# Sch.net
KiCad netlist of a schematic drawn in Altium Designer
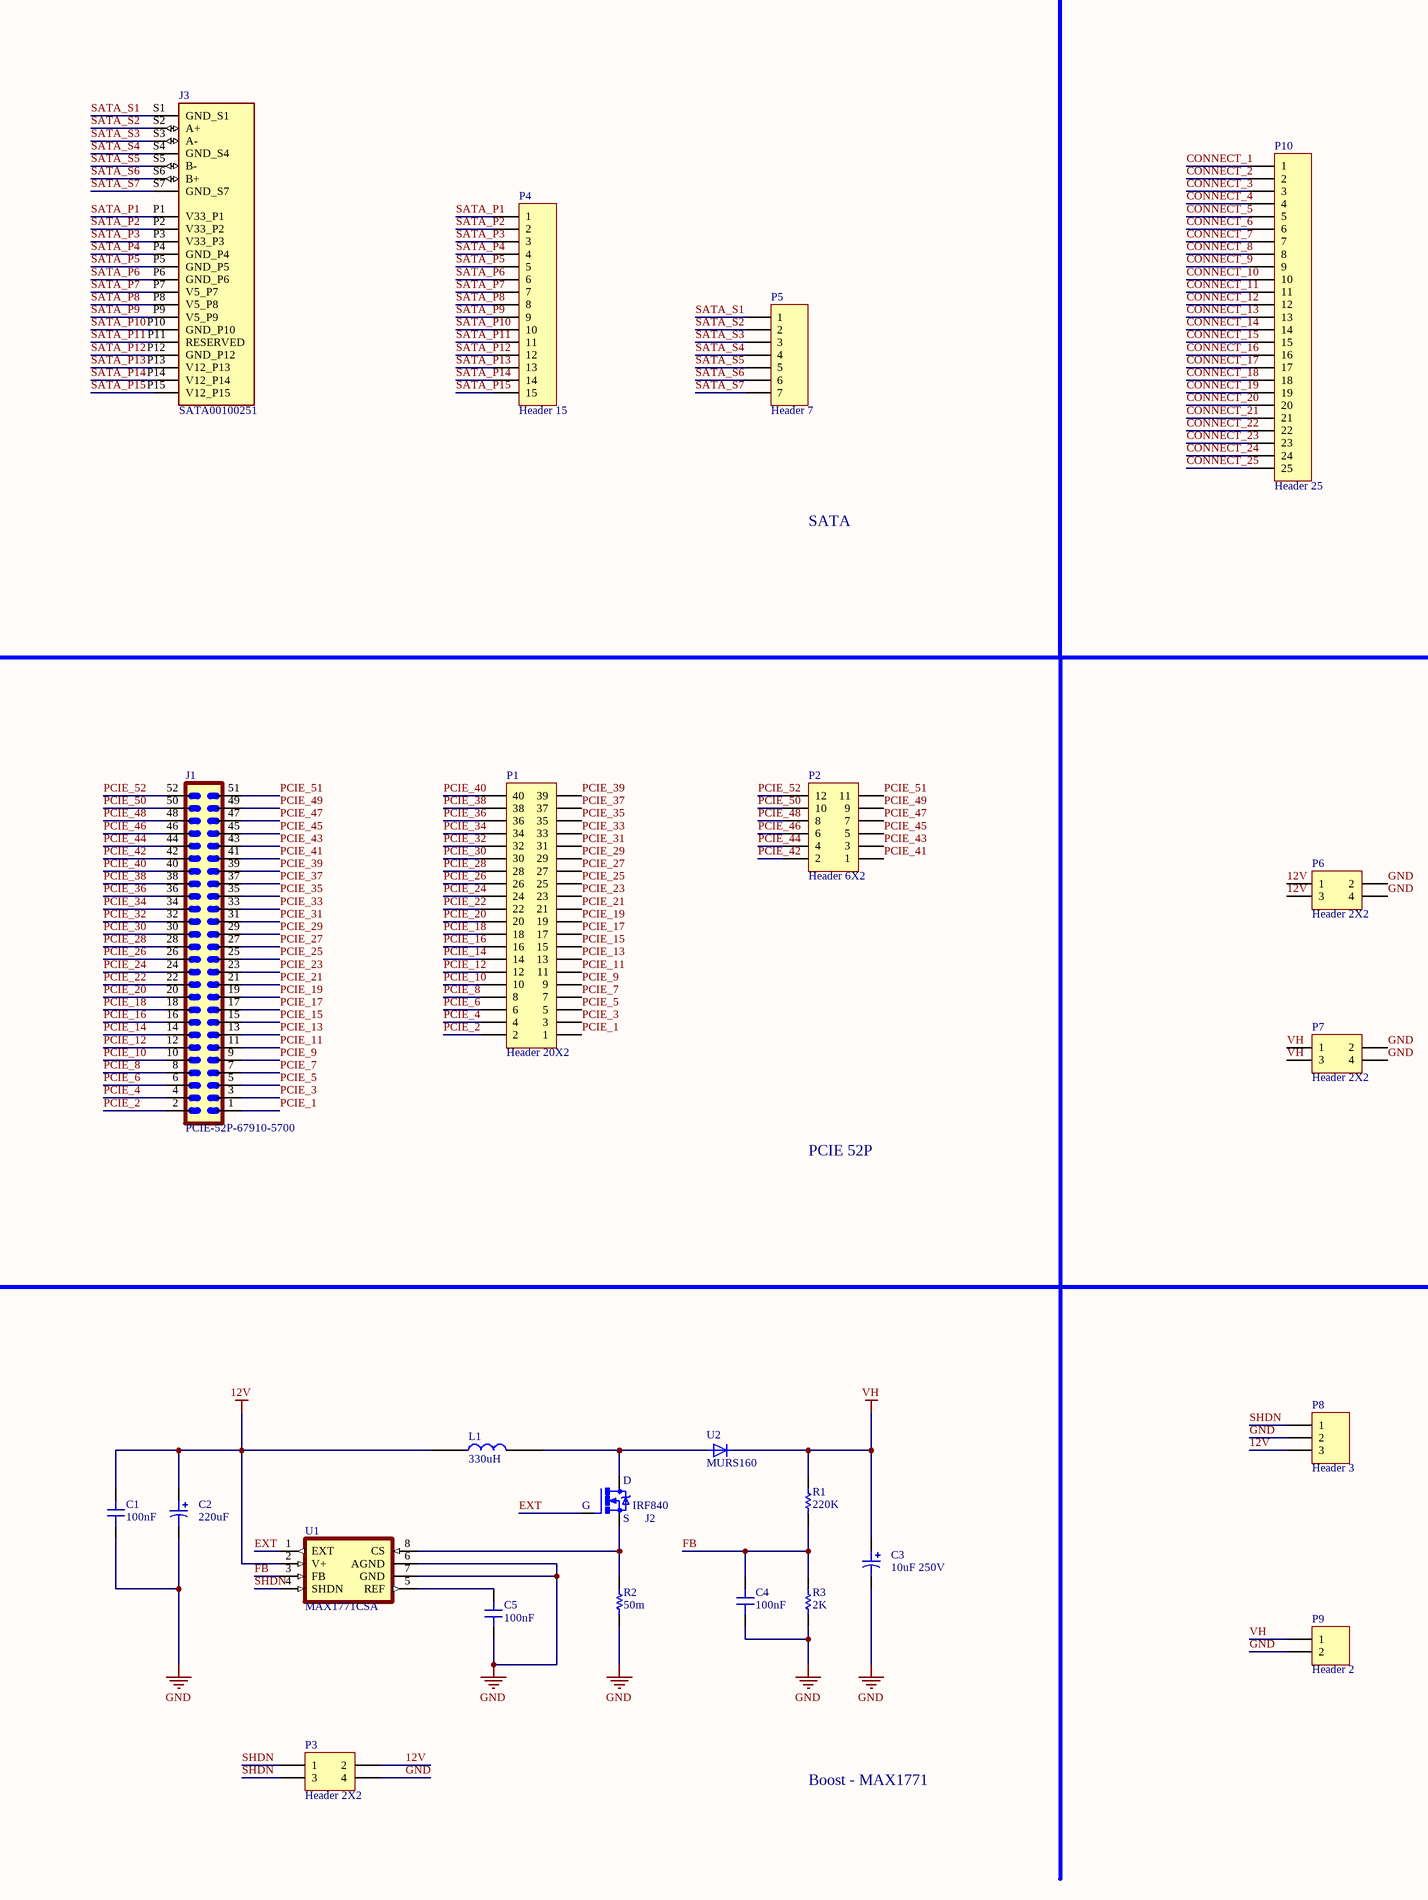
[diagram p0: Sch.SchDoc, left]
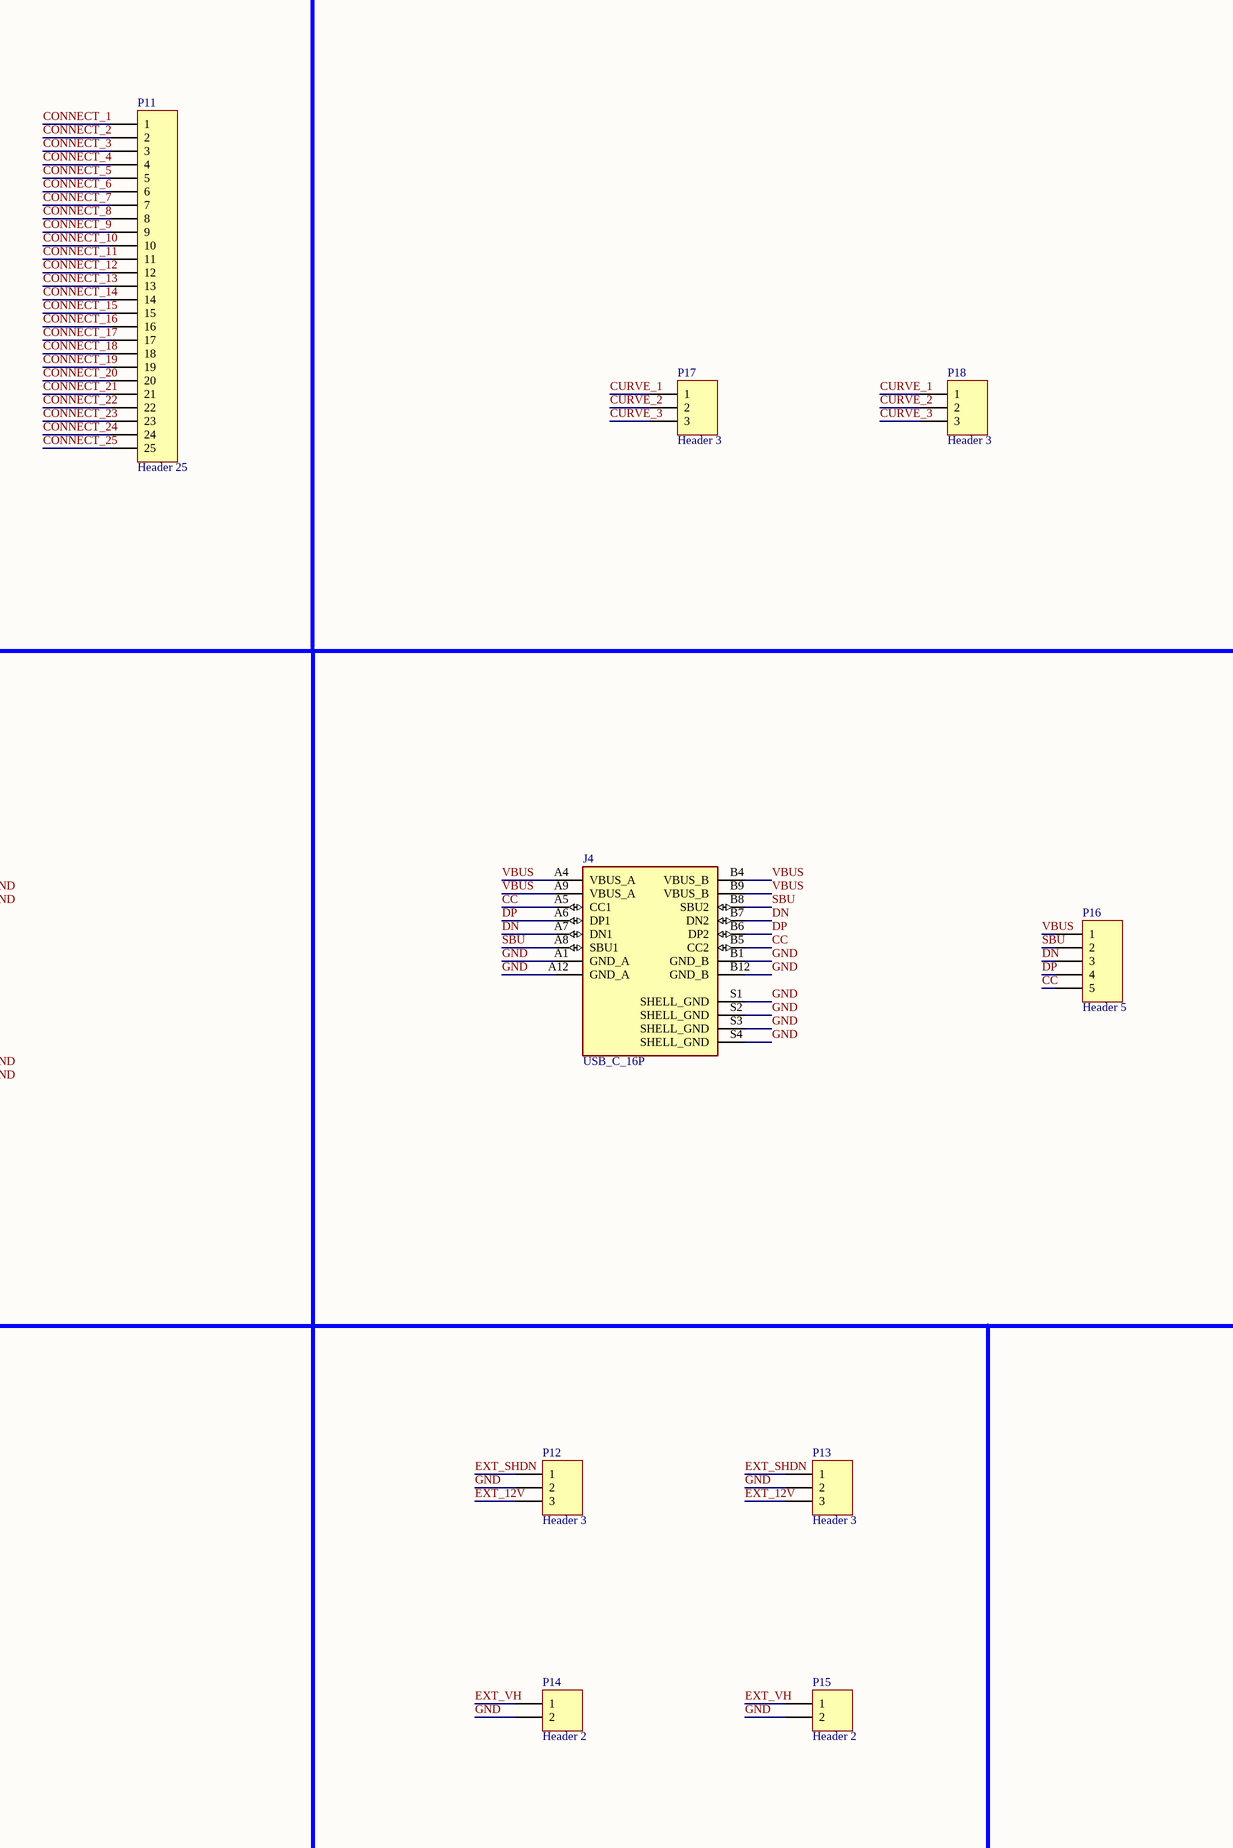
[diagram p1: Sch.SchDoc, right]

(export (version "E")
  (design (tool "Eeschema 10.0.6"))
  (components
    (comp (ref "C1") (value "100nF") (footprint "0805") (libsource (lib "Basic") (part "Capacitor")))
    (comp (ref "C2")
      (value "220uF")
      (footprint "CAPAE7666X77M_6-3x7-7")
      (libsource (lib "Basic") (part "CapacitorPolarized"))
    )
    (comp (ref "C3")
      (value "10uF 250V")
      (footprint "CAPAE113103X125M_10x12-5")
      (libsource (lib "Basic") (part "CapacitorPolarized"))
    )
    (comp (ref "C4") (value "100nF") (footprint "0805") (libsource (lib "Basic") (part "Capacitor")))
    (comp (ref "C5") (value "100nF") (footprint "0805") (libsource (lib "Basic") (part "Capacitor")))
    (comp (ref "J1")
      (value "PCIE-52P-67910-5700")
      (footprint "PCIE-52P-67910-5700")
      (description "Conn Mini PCI Express Card Edge F 52 POS 0.8mm Solder RA SMD Mini PCI Express Embossed T/R")
      (fields (field (name "MP") "67910-5700"))
      (libsource (lib "Connector") (part "PCIE-52P-67910-5700"))
    )
    (comp (ref "J2")
      (value "IRF840")
      (footprint "TO220V")
      (description "N-Channel 500 V 8A (Tc) 3.1W (Tc) Through Hole TO-220FP")
      (fields (field (name "MF") "STMicroelectronics") (field (name "MP") "IRF630"))
      (libsource (lib "Ic") (part "IRF840"))
    )
    (comp (ref "J3")
      (value "SATA00100251")
      (footprint "AMPHENOL_SATA00100251")
      (description "I/O Connectors SATA RA PLUG")
      (fields (field (name "MF") "Amphenol FCI"))
      (libsource (lib "Connector") (part "SATA00100251"))
    )
    (comp (ref "J4")
      (value "USB_C_16P")
      (footprint "USB_C_16P_CSP-USC16-TR")
      (description "CSP-USC16-TR Valcon USB Type C Surface Mount PCB Socket")
      (fields (field (name "MF") "Valcon") (field (name "MP") "CSP-USC16-TR"))
      (libsource (lib "Connector") (part "USB_C_16P"))
    )
    (comp (ref "L1") (value "330uH") (footprint "INDP125125X80N") (libsource (lib "Basic") (part "Inductor")))
    (comp (ref "P1")
      (value "Header 20X2")
      (footprint "HDR2X20")
      (description "Header, 20-Pin, Dual row")
      (fields (field (name "PUBLISHER") "Altium Limited"))
      (libsource (lib "Connector") (part "Header 20X2"))
    )
    (comp (ref "P2")
      (value "Header 6X2")
      (footprint "HDR2X6")
      (description "Header, 6-Pin, Dual row")
      (fields (field (name "PUBLISHER") "Altium Limited"))
      (libsource (lib "Connector") (part "Header 6X2"))
    )
    (comp (ref "P3")
      (value "Header 2X2")
      (footprint "HDR2X2")
      (description "Header, 2-Pin, Dual row")
      (fields (field (name "PUBLISHER") "Altium Limited"))
      (libsource (lib "Connector") (part "Header 2X2"))
    )
    (comp (ref "P4")
      (value "Header 15")
      (footprint "HDR1X15")
      (description "Header, 15-Pin")
      (fields (field (name "PUBLISHER") "Altium Limited"))
      (libsource (lib "Connector") (part "Header 15"))
    )
    (comp (ref "P5")
      (value "Header 7")
      (footprint "HDR1X7")
      (description "Header, 7-Pin")
      (fields (field (name "PUBLISHER") "Altium Limited"))
      (libsource (lib "Connector") (part "Header 7"))
    )
    (comp (ref "P6")
      (value "Header 2X2")
      (footprint "HDR2X2")
      (description "Header, 2-Pin, Dual row")
      (fields (field (name "PUBLISHER") "Altium Limited"))
      (libsource (lib "Connector") (part "Header 2X2"))
    )
    (comp (ref "P7")
      (value "Header 2X2")
      (footprint "HDR2X2")
      (description "Header, 2-Pin, Dual row")
      (fields (field (name "PUBLISHER") "Altium Limited"))
      (libsource (lib "Connector") (part "Header 2X2"))
    )
    (comp (ref "P8")
      (value "Header 3")
      (footprint "HDR1X3")
      (description "Header, 3-Pin")
      (fields (field (name "PUBLISHER") "Altium Limited"))
      (libsource (lib "Connector") (part "Header 3"))
    )
    (comp (ref "P9")
      (value "Header 2")
      (footprint "HDR1X2")
      (description "Header, 2-Pin")
      (fields (field (name "PUBLISHER") "Altium Limited"))
      (libsource (lib "Connector") (part "Header 2"))
    )
    (comp (ref "P10")
      (value "Header 25")
      (footprint "HDR1X25")
      (description "Header, 25-Pin")
      (fields (field (name "PUBLISHER") "Altium Limited"))
      (libsource (lib "Connector") (part "Header 25"))
    )
    (comp (ref "P11")
      (value "Header 25")
      (footprint "HDR1X25")
      (description "Header, 25-Pin")
      (fields (field (name "PUBLISHER") "Altium Limited"))
      (libsource (lib "Connector") (part "Header 25"))
    )
    (comp (ref "P12")
      (value "Header 3")
      (footprint "HDR1X3")
      (description "Header, 3-Pin")
      (fields (field (name "PUBLISHER") "Altium Limited"))
      (libsource (lib "Connector") (part "Header 3"))
    )
    (comp (ref "P13")
      (value "Header 3")
      (footprint "HDR1X3")
      (description "Header, 3-Pin")
      (fields (field (name "PUBLISHER") "Altium Limited"))
      (libsource (lib "Connector") (part "Header 3"))
    )
    (comp (ref "P14")
      (value "Header 2")
      (footprint "HDR1X2")
      (description "Header, 2-Pin")
      (fields (field (name "PUBLISHER") "Altium Limited"))
      (libsource (lib "Connector") (part "Header 2"))
    )
    (comp (ref "P15")
      (value "Header 2")
      (footprint "HDR1X2")
      (description "Header, 2-Pin")
      (fields (field (name "PUBLISHER") "Altium Limited"))
      (libsource (lib "Connector") (part "Header 2"))
    )
    (comp (ref "P16")
      (value "Header 5")
      (footprint "HDR1X5")
      (description "Header, 5-Pin")
      (fields (field (name "PUBLISHER") "Altium Limited"))
      (libsource (lib "Connector") (part "Header 5"))
    )
    (comp (ref "P17")
      (value "Header 3")
      (footprint "HDR1X3")
      (description "Header, 3-Pin")
      (fields (field (name "PUBLISHER") "Altium Limited"))
      (libsource (lib "Connector") (part "Header 3"))
    )
    (comp (ref "P18")
      (value "Header 3")
      (footprint "HDR1X3")
      (description "Header, 3-Pin")
      (fields (field (name "PUBLISHER") "Altium Limited"))
      (libsource (lib "Connector") (part "Header 3"))
    )
    (comp (ref "R1") (value "220K") (footprint "0805") (libsource (lib "Basic") (part "Resistor")))
    (comp (ref "R2") (value "50m") (footprint "0805") (libsource (lib "Basic") (part "Resistor")))
    (comp (ref "R3") (value "2K") (footprint "0805") (libsource (lib "Basic") (part "Resistor")))
    (comp (ref "U1")
      (value "MAX1771CSA")
      (footprint "MAX1771CSA")
      (fields (field (name "MF") "Maxim Integrated"))
      (libsource (lib "Ic") (part "MAX1771CSA"))
    )
    (comp (ref "U2")
      (value "MURS160")
      (footprint "MURS160")
      (description "Diode Standard 600V 1A Surface Mount SMB")
      (fields (field (name "MF") "World Products"))
      (libsource (lib "Ic") (part "MURS160"))
    )
  )
  (nets
    (net (code "1") (name "/CC") (class "Default")
      (node (ref "J4") (pin "A5") (pinfunction "CC1_A5") (pintype "bidirectional"))
      (node (ref "J4") (pin "B5") (pinfunction "CC2_B5") (pintype "bidirectional"))
      (node (ref "P16") (pin "5") (pinfunction "5_5") (pintype "passive"))
    )
    (net (code "2") (name "/CONNECT_1") (class "Default")
      (node (ref "P10") (pin "1") (pinfunction "1_1") (pintype "passive"))
      (node (ref "P11") (pin "1") (pinfunction "1_1") (pintype "passive"))
    )
    (net (code "3") (name "/CONNECT_2") (class "Default")
      (node (ref "P10") (pin "2") (pinfunction "2_2") (pintype "passive"))
      (node (ref "P11") (pin "2") (pinfunction "2_2") (pintype "passive"))
    )
    (net (code "4") (name "/CONNECT_3") (class "Default")
      (node (ref "P10") (pin "3") (pinfunction "3_3") (pintype "passive"))
      (node (ref "P11") (pin "3") (pinfunction "3_3") (pintype "passive"))
    )
    (net (code "5") (name "/CONNECT_4") (class "Default")
      (node (ref "P10") (pin "4") (pinfunction "4_4") (pintype "passive"))
      (node (ref "P11") (pin "4") (pinfunction "4_4") (pintype "passive"))
    )
    (net (code "6") (name "/CONNECT_5") (class "Default")
      (node (ref "P10") (pin "5") (pinfunction "5_5") (pintype "passive"))
      (node (ref "P11") (pin "5") (pinfunction "5_5") (pintype "passive"))
    )
    (net (code "7") (name "/CONNECT_6") (class "Default")
      (node (ref "P10") (pin "6") (pinfunction "6_6") (pintype "passive"))
      (node (ref "P11") (pin "6") (pinfunction "6_6") (pintype "passive"))
    )
    (net (code "8") (name "/CONNECT_7") (class "Default")
      (node (ref "P10") (pin "7") (pinfunction "7_7") (pintype "passive"))
      (node (ref "P11") (pin "7") (pinfunction "7_7") (pintype "passive"))
    )
    (net (code "9") (name "/CONNECT_8") (class "Default")
      (node (ref "P10") (pin "8") (pinfunction "8_8") (pintype "passive"))
      (node (ref "P11") (pin "8") (pinfunction "8_8") (pintype "passive"))
    )
    (net (code "10") (name "/CONNECT_9") (class "Default")
      (node (ref "P10") (pin "9") (pinfunction "9_9") (pintype "passive"))
      (node (ref "P11") (pin "9") (pinfunction "9_9") (pintype "passive"))
    )
    (net (code "11") (name "/CONNECT_10") (class "Default")
      (node (ref "P10") (pin "10") (pinfunction "10_10") (pintype "passive"))
      (node (ref "P11") (pin "10") (pinfunction "10_10") (pintype "passive"))
    )
    (net (code "12") (name "/CONNECT_11") (class "Default")
      (node (ref "P10") (pin "11") (pinfunction "11_11") (pintype "passive"))
      (node (ref "P11") (pin "11") (pinfunction "11_11") (pintype "passive"))
    )
    (net (code "13") (name "/CONNECT_12") (class "Default")
      (node (ref "P10") (pin "12") (pinfunction "12_12") (pintype "passive"))
      (node (ref "P11") (pin "12") (pinfunction "12_12") (pintype "passive"))
    )
    (net (code "14") (name "/CONNECT_13") (class "Default")
      (node (ref "P10") (pin "13") (pinfunction "13_13") (pintype "passive"))
      (node (ref "P11") (pin "13") (pinfunction "13_13") (pintype "passive"))
    )
    (net (code "15") (name "/CONNECT_14") (class "Default")
      (node (ref "P10") (pin "14") (pinfunction "14_14") (pintype "passive"))
      (node (ref "P11") (pin "14") (pinfunction "14_14") (pintype "passive"))
    )
    (net (code "16") (name "/CONNECT_15") (class "Default")
      (node (ref "P10") (pin "15") (pinfunction "15_15") (pintype "passive"))
      (node (ref "P11") (pin "15") (pinfunction "15_15") (pintype "passive"))
    )
    (net (code "17") (name "/CONNECT_16") (class "Default")
      (node (ref "P10") (pin "16") (pinfunction "16_16") (pintype "passive"))
      (node (ref "P11") (pin "16") (pinfunction "16_16") (pintype "passive"))
    )
    (net (code "18") (name "/CONNECT_17") (class "Default")
      (node (ref "P10") (pin "17") (pinfunction "17_17") (pintype "passive"))
      (node (ref "P11") (pin "17") (pinfunction "17_17") (pintype "passive"))
    )
    (net (code "19") (name "/CONNECT_18") (class "Default")
      (node (ref "P10") (pin "18") (pinfunction "18_18") (pintype "passive"))
      (node (ref "P11") (pin "18") (pinfunction "18_18") (pintype "passive"))
    )
    (net (code "20") (name "/CONNECT_19") (class "Default")
      (node (ref "P10") (pin "19") (pinfunction "19_19") (pintype "passive"))
      (node (ref "P11") (pin "19") (pinfunction "19_19") (pintype "passive"))
    )
    (net (code "21") (name "/CONNECT_20") (class "Default")
      (node (ref "P10") (pin "20") (pinfunction "20_20") (pintype "passive"))
      (node (ref "P11") (pin "20") (pinfunction "20_20") (pintype "passive"))
    )
    (net (code "22") (name "/CONNECT_21") (class "Default")
      (node (ref "P10") (pin "21") (pinfunction "21_21") (pintype "passive"))
      (node (ref "P11") (pin "21") (pinfunction "21_21") (pintype "passive"))
    )
    (net (code "23") (name "/CONNECT_22") (class "Default")
      (node (ref "P10") (pin "22") (pinfunction "22_22") (pintype "passive"))
      (node (ref "P11") (pin "22") (pinfunction "22_22") (pintype "passive"))
    )
    (net (code "24") (name "/CONNECT_23") (class "Default")
      (node (ref "P10") (pin "23") (pinfunction "23_23") (pintype "passive"))
      (node (ref "P11") (pin "23") (pinfunction "23_23") (pintype "passive"))
    )
    (net (code "25") (name "/CONNECT_24") (class "Default")
      (node (ref "P10") (pin "24") (pinfunction "24_24") (pintype "passive"))
      (node (ref "P11") (pin "24") (pinfunction "24_24") (pintype "passive"))
    )
    (net (code "26") (name "/CONNECT_25") (class "Default")
      (node (ref "P10") (pin "25") (pinfunction "25_25") (pintype "passive"))
      (node (ref "P11") (pin "25") (pinfunction "25_25") (pintype "passive"))
    )
    (net (code "27") (name "/CURVE_1") (class "Default")
      (node (ref "P17") (pin "1") (pinfunction "1_1") (pintype "passive"))
      (node (ref "P18") (pin "1") (pinfunction "1_1") (pintype "passive"))
    )
    (net (code "28") (name "/CURVE_2") (class "Default")
      (node (ref "P17") (pin "2") (pinfunction "2_2") (pintype "passive"))
      (node (ref "P18") (pin "2") (pinfunction "2_2") (pintype "passive"))
    )
    (net (code "29") (name "/CURVE_3") (class "Default")
      (node (ref "P17") (pin "3") (pinfunction "3_3") (pintype "passive"))
      (node (ref "P18") (pin "3") (pinfunction "3_3") (pintype "passive"))
    )
    (net (code "30") (name "/DN") (class "Default")
      (node (ref "J4") (pin "A7") (pinfunction "DN1_A7") (pintype "bidirectional"))
      (node (ref "J4") (pin "B7") (pinfunction "DN2_B7") (pintype "bidirectional"))
      (node (ref "P16") (pin "3") (pinfunction "3_3") (pintype "passive"))
    )
    (net (code "31") (name "/DP") (class "Default")
      (node (ref "J4") (pin "A6") (pinfunction "DP1_A6") (pintype "bidirectional"))
      (node (ref "J4") (pin "B6") (pinfunction "DP2_B6") (pintype "bidirectional"))
      (node (ref "P16") (pin "4") (pinfunction "4_4") (pintype "passive"))
    )
    (net (code "32") (name "/EXT") (class "Default")
      (node (ref "J2") (pin "1") (pinfunction "G_1") (pintype "passive"))
      (node (ref "U1") (pin "1") (pinfunction "EXT_1") (pintype "output"))
    )
    (net (code "33") (name "/EXT_12V") (class "Default")
      (node (ref "P12") (pin "3") (pinfunction "3_3") (pintype "passive"))
      (node (ref "P13") (pin "3") (pinfunction "3_3") (pintype "passive"))
    )
    (net (code "34") (name "/EXT_SHDN") (class "Default")
      (node (ref "P12") (pin "1") (pinfunction "1_1") (pintype "passive"))
      (node (ref "P13") (pin "1") (pinfunction "1_1") (pintype "passive"))
    )
    (net (code "35") (name "/EXT_VH") (class "Default")
      (node (ref "P14") (pin "1") (pinfunction "1_1") (pintype "passive"))
      (node (ref "P15") (pin "1") (pinfunction "1_1") (pintype "passive"))
    )
    (net (code "36") (name "/FB") (class "Default")
      (node (ref "C4") (pin "1") (pinfunction "1_1") (pintype "passive"))
      (node (ref "R1") (pin "2") (pinfunction "2_2") (pintype "passive"))
      (node (ref "R3") (pin "1") (pinfunction "1_1") (pintype "passive"))
      (node (ref "U1") (pin "3") (pinfunction "FB_3") (pintype "input"))
    )
    (net (code "37") (name "/PCIE_1") (class "Default")
      (node (ref "J1") (pin "1") (pinfunction "1_1") (pintype "passive"))
      (node (ref "P1") (pin "1") (pinfunction "1_1") (pintype "passive"))
    )
    (net (code "38") (name "/PCIE_2") (class "Default")
      (node (ref "J1") (pin "2") (pinfunction "2_2") (pintype "passive"))
      (node (ref "P1") (pin "2") (pinfunction "2_2") (pintype "passive"))
    )
    (net (code "39") (name "/PCIE_3") (class "Default")
      (node (ref "J1") (pin "3") (pinfunction "3_3") (pintype "passive"))
      (node (ref "P1") (pin "3") (pinfunction "3_3") (pintype "passive"))
    )
    (net (code "40") (name "/PCIE_4") (class "Default")
      (node (ref "J1") (pin "4") (pinfunction "4_4") (pintype "passive"))
      (node (ref "P1") (pin "4") (pinfunction "4_4") (pintype "passive"))
    )
    (net (code "41") (name "/PCIE_5") (class "Default")
      (node (ref "J1") (pin "5") (pinfunction "5_5") (pintype "passive"))
      (node (ref "P1") (pin "5") (pinfunction "5_5") (pintype "passive"))
    )
    (net (code "42") (name "/PCIE_6") (class "Default")
      (node (ref "J1") (pin "6") (pinfunction "6_6") (pintype "passive"))
      (node (ref "P1") (pin "6") (pinfunction "6_6") (pintype "passive"))
    )
    (net (code "43") (name "/PCIE_7") (class "Default")
      (node (ref "J1") (pin "7") (pinfunction "7_7") (pintype "passive"))
      (node (ref "P1") (pin "7") (pinfunction "7_7") (pintype "passive"))
    )
    (net (code "44") (name "/PCIE_8") (class "Default")
      (node (ref "J1") (pin "8") (pinfunction "8_8") (pintype "passive"))
      (node (ref "P1") (pin "8") (pinfunction "8_8") (pintype "passive"))
    )
    (net (code "45") (name "/PCIE_9") (class "Default")
      (node (ref "J1") (pin "9") (pinfunction "9_9") (pintype "passive"))
      (node (ref "P1") (pin "9") (pinfunction "9_9") (pintype "passive"))
    )
    (net (code "46") (name "/PCIE_10") (class "Default")
      (node (ref "J1") (pin "10") (pinfunction "10_10") (pintype "passive"))
      (node (ref "P1") (pin "10") (pinfunction "10_10") (pintype "passive"))
    )
    (net (code "47") (name "/PCIE_11") (class "Default")
      (node (ref "J1") (pin "11") (pinfunction "11_11") (pintype "passive"))
      (node (ref "P1") (pin "11") (pinfunction "11_11") (pintype "passive"))
    )
    (net (code "48") (name "/PCIE_12") (class "Default")
      (node (ref "J1") (pin "12") (pinfunction "12_12") (pintype "passive"))
      (node (ref "P1") (pin "12") (pinfunction "12_12") (pintype "passive"))
    )
    (net (code "49") (name "/PCIE_13") (class "Default")
      (node (ref "J1") (pin "13") (pinfunction "13_13") (pintype "passive"))
      (node (ref "P1") (pin "13") (pinfunction "13_13") (pintype "passive"))
    )
    (net (code "50") (name "/PCIE_14") (class "Default")
      (node (ref "J1") (pin "14") (pinfunction "14_14") (pintype "passive"))
      (node (ref "P1") (pin "14") (pinfunction "14_14") (pintype "passive"))
    )
    (net (code "51") (name "/PCIE_15") (class "Default")
      (node (ref "J1") (pin "15") (pinfunction "15_15") (pintype "passive"))
      (node (ref "P1") (pin "15") (pinfunction "15_15") (pintype "passive"))
    )
    (net (code "52") (name "/PCIE_16") (class "Default")
      (node (ref "J1") (pin "16") (pinfunction "16_16") (pintype "passive"))
      (node (ref "P1") (pin "16") (pinfunction "16_16") (pintype "passive"))
    )
    (net (code "53") (name "/PCIE_17") (class "Default")
      (node (ref "J1") (pin "17") (pinfunction "17_17") (pintype "passive"))
      (node (ref "P1") (pin "17") (pinfunction "17_17") (pintype "passive"))
    )
    (net (code "54") (name "/PCIE_18") (class "Default")
      (node (ref "J1") (pin "18") (pinfunction "18_18") (pintype "passive"))
      (node (ref "P1") (pin "18") (pinfunction "18_18") (pintype "passive"))
    )
    (net (code "55") (name "/PCIE_19") (class "Default")
      (node (ref "J1") (pin "19") (pinfunction "19_19") (pintype "passive"))
      (node (ref "P1") (pin "19") (pinfunction "19_19") (pintype "passive"))
    )
    (net (code "56") (name "/PCIE_20") (class "Default")
      (node (ref "J1") (pin "20") (pinfunction "20_20") (pintype "passive"))
      (node (ref "P1") (pin "20") (pinfunction "20_20") (pintype "passive"))
    )
    (net (code "57") (name "/PCIE_21") (class "Default")
      (node (ref "J1") (pin "21") (pinfunction "21_21") (pintype "passive"))
      (node (ref "P1") (pin "21") (pinfunction "21_21") (pintype "passive"))
    )
    (net (code "58") (name "/PCIE_22") (class "Default")
      (node (ref "J1") (pin "22") (pinfunction "22_22") (pintype "passive"))
      (node (ref "P1") (pin "22") (pinfunction "22_22") (pintype "passive"))
    )
    (net (code "59") (name "/PCIE_23") (class "Default")
      (node (ref "J1") (pin "23") (pinfunction "23_23") (pintype "passive"))
      (node (ref "P1") (pin "23") (pinfunction "23_23") (pintype "passive"))
    )
    (net (code "60") (name "/PCIE_24") (class "Default")
      (node (ref "J1") (pin "24") (pinfunction "24_24") (pintype "passive"))
      (node (ref "P1") (pin "24") (pinfunction "24_24") (pintype "passive"))
    )
    (net (code "61") (name "/PCIE_25") (class "Default")
      (node (ref "J1") (pin "25") (pinfunction "25_25") (pintype "passive"))
      (node (ref "P1") (pin "25") (pinfunction "25_25") (pintype "passive"))
    )
    (net (code "62") (name "/PCIE_26") (class "Default")
      (node (ref "J1") (pin "26") (pinfunction "26_26") (pintype "passive"))
      (node (ref "P1") (pin "26") (pinfunction "26_26") (pintype "passive"))
    )
    (net (code "63") (name "/PCIE_27") (class "Default")
      (node (ref "J1") (pin "27") (pinfunction "27_27") (pintype "passive"))
      (node (ref "P1") (pin "27") (pinfunction "27_27") (pintype "passive"))
    )
    (net (code "64") (name "/PCIE_28") (class "Default")
      (node (ref "J1") (pin "28") (pinfunction "28_28") (pintype "passive"))
      (node (ref "P1") (pin "28") (pinfunction "28_28") (pintype "passive"))
    )
    (net (code "65") (name "/PCIE_29") (class "Default")
      (node (ref "J1") (pin "29") (pinfunction "29_29") (pintype "passive"))
      (node (ref "P1") (pin "29") (pinfunction "29_29") (pintype "passive"))
    )
    (net (code "66") (name "/PCIE_30") (class "Default")
      (node (ref "J1") (pin "30") (pinfunction "30_30") (pintype "passive"))
      (node (ref "P1") (pin "30") (pinfunction "30_30") (pintype "passive"))
    )
    (net (code "67") (name "/PCIE_31") (class "Default")
      (node (ref "J1") (pin "31") (pinfunction "31_31") (pintype "passive"))
      (node (ref "P1") (pin "31") (pinfunction "31_31") (pintype "passive"))
    )
    (net (code "68") (name "/PCIE_32") (class "Default")
      (node (ref "J1") (pin "32") (pinfunction "32_32") (pintype "passive"))
      (node (ref "P1") (pin "32") (pinfunction "32_32") (pintype "passive"))
    )
    (net (code "69") (name "/PCIE_33") (class "Default")
      (node (ref "J1") (pin "33") (pinfunction "33_33") (pintype "passive"))
      (node (ref "P1") (pin "33") (pinfunction "33_33") (pintype "passive"))
    )
    (net (code "70") (name "/PCIE_34") (class "Default")
      (node (ref "J1") (pin "34") (pinfunction "34_34") (pintype "passive"))
      (node (ref "P1") (pin "34") (pinfunction "34_34") (pintype "passive"))
    )
    (net (code "71") (name "/PCIE_35") (class "Default")
      (node (ref "J1") (pin "35") (pinfunction "35_35") (pintype "passive"))
      (node (ref "P1") (pin "35") (pinfunction "35_35") (pintype "passive"))
    )
    (net (code "72") (name "/PCIE_36") (class "Default")
      (node (ref "J1") (pin "36") (pinfunction "36_36") (pintype "passive"))
      (node (ref "P1") (pin "36") (pinfunction "36_36") (pintype "passive"))
    )
    (net (code "73") (name "/PCIE_37") (class "Default")
      (node (ref "J1") (pin "37") (pinfunction "37_37") (pintype "passive"))
      (node (ref "P1") (pin "37") (pinfunction "37_37") (pintype "passive"))
    )
    (net (code "74") (name "/PCIE_38") (class "Default")
      (node (ref "J1") (pin "38") (pinfunction "38_38") (pintype "passive"))
      (node (ref "P1") (pin "38") (pinfunction "38_38") (pintype "passive"))
    )
    (net (code "75") (name "/PCIE_39") (class "Default")
      (node (ref "J1") (pin "39") (pinfunction "39_39") (pintype "passive"))
      (node (ref "P1") (pin "39") (pinfunction "39_39") (pintype "passive"))
    )
    (net (code "76") (name "/PCIE_40") (class "Default")
      (node (ref "J1") (pin "40") (pinfunction "40_40") (pintype "passive"))
      (node (ref "P1") (pin "40") (pinfunction "40_40") (pintype "passive"))
    )
    (net (code "77") (name "/PCIE_41") (class "Default")
      (node (ref "J1") (pin "41") (pinfunction "41_41") (pintype "passive"))
      (node (ref "P2") (pin "1") (pinfunction "1_1") (pintype "passive"))
    )
    (net (code "78") (name "/PCIE_42") (class "Default")
      (node (ref "J1") (pin "42") (pinfunction "42_42") (pintype "passive"))
      (node (ref "P2") (pin "2") (pinfunction "2_2") (pintype "passive"))
    )
    (net (code "79") (name "/PCIE_43") (class "Default")
      (node (ref "J1") (pin "43") (pinfunction "43_43") (pintype "passive"))
      (node (ref "P2") (pin "3") (pinfunction "3_3") (pintype "passive"))
    )
    (net (code "80") (name "/PCIE_44") (class "Default")
      (node (ref "J1") (pin "44") (pinfunction "44_44") (pintype "passive"))
      (node (ref "P2") (pin "4") (pinfunction "4_4") (pintype "passive"))
    )
    (net (code "81") (name "/PCIE_45") (class "Default")
      (node (ref "J1") (pin "45") (pinfunction "45_45") (pintype "passive"))
      (node (ref "P2") (pin "5") (pinfunction "5_5") (pintype "passive"))
    )
    (net (code "82") (name "/PCIE_46") (class "Default")
      (node (ref "J1") (pin "46") (pinfunction "46_46") (pintype "passive"))
      (node (ref "P2") (pin "6") (pinfunction "6_6") (pintype "passive"))
    )
    (net (code "83") (name "/PCIE_47") (class "Default")
      (node (ref "J1") (pin "47") (pinfunction "47_47") (pintype "passive"))
      (node (ref "P2") (pin "7") (pinfunction "7_7") (pintype "passive"))
    )
    (net (code "84") (name "/PCIE_48") (class "Default")
      (node (ref "J1") (pin "48") (pinfunction "48_48") (pintype "passive"))
      (node (ref "P2") (pin "8") (pinfunction "8_8") (pintype "passive"))
    )
    (net (code "85") (name "/PCIE_49") (class "Default")
      (node (ref "J1") (pin "49") (pinfunction "49_49") (pintype "passive"))
      (node (ref "P2") (pin "9") (pinfunction "9_9") (pintype "passive"))
    )
    (net (code "86") (name "/PCIE_50") (class "Default")
      (node (ref "J1") (pin "50") (pinfunction "50_50") (pintype "passive"))
      (node (ref "P2") (pin "10") (pinfunction "10_10") (pintype "passive"))
    )
    (net (code "87") (name "/PCIE_51") (class "Default")
      (node (ref "J1") (pin "51") (pinfunction "51_51") (pintype "passive"))
      (node (ref "P2") (pin "11") (pinfunction "11_11") (pintype "passive"))
    )
    (net (code "88") (name "/PCIE_52") (class "Default")
      (node (ref "J1") (pin "52") (pinfunction "52_52") (pintype "passive"))
      (node (ref "P2") (pin "12") (pinfunction "12_12") (pintype "passive"))
    )
    (net (code "89") (name "/SATA_P1") (class "Default")
      (node (ref "J3") (pin "P1") (pinfunction "V33_P1_P1") (pintype "power_in"))
      (node (ref "P4") (pin "1") (pinfunction "1_1") (pintype "passive"))
    )
    (net (code "90") (name "/SATA_P2") (class "Default")
      (node (ref "J3") (pin "P2") (pinfunction "V33_P2_P2") (pintype "power_in"))
      (node (ref "P4") (pin "2") (pinfunction "2_2") (pintype "passive"))
    )
    (net (code "91") (name "/SATA_P3") (class "Default")
      (node (ref "J3") (pin "P3") (pinfunction "V33_P3_P3") (pintype "power_in"))
      (node (ref "P4") (pin "3") (pinfunction "3_3") (pintype "passive"))
    )
    (net (code "92") (name "/SATA_P4") (class "Default")
      (node (ref "J3") (pin "P4") (pinfunction "GND_P4_P4") (pintype "power_in"))
      (node (ref "P4") (pin "4") (pinfunction "4_4") (pintype "passive"))
    )
    (net (code "93") (name "/SATA_P5") (class "Default")
      (node (ref "J3") (pin "P5") (pinfunction "GND_P5_P5") (pintype "power_in"))
      (node (ref "P4") (pin "5") (pinfunction "5_5") (pintype "passive"))
    )
    (net (code "94") (name "/SATA_P6") (class "Default")
      (node (ref "J3") (pin "P6") (pinfunction "GND_P6_P6") (pintype "power_in"))
      (node (ref "P4") (pin "6") (pinfunction "6_6") (pintype "passive"))
    )
    (net (code "95") (name "/SATA_P7") (class "Default")
      (node (ref "J3") (pin "P7") (pinfunction "V5_P7_P7") (pintype "power_in"))
      (node (ref "P4") (pin "7") (pinfunction "7_7") (pintype "passive"))
    )
    (net (code "96") (name "/SATA_P8") (class "Default")
      (node (ref "J3") (pin "P8") (pinfunction "V5_P8_P8") (pintype "power_in"))
      (node (ref "P4") (pin "8") (pinfunction "8_8") (pintype "passive"))
    )
    (net (code "97") (name "/SATA_P9") (class "Default")
      (node (ref "J3") (pin "P9") (pinfunction "V5_P9_P9") (pintype "power_in"))
      (node (ref "P4") (pin "9") (pinfunction "9_9") (pintype "passive"))
    )
    (net (code "98") (name "/SATA_P10") (class "Default")
      (node (ref "J3") (pin "P10") (pinfunction "GND_P10_P10") (pintype "power_in"))
      (node (ref "P4") (pin "10") (pinfunction "10_10") (pintype "passive"))
    )
    (net (code "99") (name "/SATA_P11") (class "Default")
      (node (ref "J3") (pin "P11") (pinfunction "RESERVED_P11") (pintype "passive"))
      (node (ref "P4") (pin "11") (pinfunction "11_11") (pintype "passive"))
    )
    (net (code "100") (name "/SATA_P12") (class "Default")
      (node (ref "J3") (pin "P12") (pinfunction "GND_P12_P12") (pintype "power_in"))
      (node (ref "P4") (pin "12") (pinfunction "12_12") (pintype "passive"))
    )
    (net (code "101") (name "/SATA_P13") (class "Default")
      (node (ref "J3") (pin "P13") (pinfunction "V12_P13_P13") (pintype "power_in"))
      (node (ref "P4") (pin "13") (pinfunction "13_13") (pintype "passive"))
    )
    (net (code "102") (name "/SATA_P14") (class "Default")
      (node (ref "J3") (pin "P14") (pinfunction "V12_P14_P14") (pintype "power_in"))
      (node (ref "P4") (pin "14") (pinfunction "14_14") (pintype "passive"))
    )
    (net (code "103") (name "/SATA_P15") (class "Default")
      (node (ref "J3") (pin "P15") (pinfunction "V12_P15_P15") (pintype "power_in"))
      (node (ref "P4") (pin "15") (pinfunction "15_15") (pintype "passive"))
    )
    (net (code "104") (name "/SATA_S1") (class "Default")
      (node (ref "J3") (pin "S1") (pinfunction "GND_S1_S1") (pintype "power_in"))
      (node (ref "P5") (pin "1") (pinfunction "1_1") (pintype "passive"))
    )
    (net (code "105") (name "/SATA_S2") (class "Default")
      (node (ref "J3") (pin "S2") (pinfunction "A+_S2") (pintype "bidirectional"))
      (node (ref "P5") (pin "2") (pinfunction "2_2") (pintype "passive"))
    )
    (net (code "106") (name "/SATA_S3") (class "Default")
      (node (ref "J3") (pin "S3") (pinfunction "A-_S3") (pintype "bidirectional"))
      (node (ref "P5") (pin "3") (pinfunction "3_3") (pintype "passive"))
    )
    (net (code "107") (name "/SATA_S4") (class "Default")
      (node (ref "J3") (pin "S4") (pinfunction "GND_S4_S4") (pintype "power_in"))
      (node (ref "P5") (pin "4") (pinfunction "4_4") (pintype "passive"))
    )
    (net (code "108") (name "/SATA_S5") (class "Default")
      (node (ref "J3") (pin "S5") (pinfunction "B-_S5") (pintype "bidirectional"))
      (node (ref "P5") (pin "5") (pinfunction "5_5") (pintype "passive"))
    )
    (net (code "109") (name "/SATA_S6") (class "Default")
      (node (ref "J3") (pin "S6") (pinfunction "B+_S6") (pintype "bidirectional"))
      (node (ref "P5") (pin "6") (pinfunction "6_6") (pintype "passive"))
    )
    (net (code "110") (name "/SATA_S7") (class "Default")
      (node (ref "J3") (pin "S7") (pinfunction "GND_S7_S7") (pintype "power_in"))
      (node (ref "P5") (pin "7") (pinfunction "7_7") (pintype "passive"))
    )
    (net (code "111") (name "/SBU") (class "Default")
      (node (ref "J4") (pin "A8") (pinfunction "SBU1_A8") (pintype "bidirectional"))
      (node (ref "J4") (pin "B8") (pinfunction "SBU2_B8") (pintype "bidirectional"))
      (node (ref "P16") (pin "2") (pinfunction "2_2") (pintype "passive"))
    )
    (net (code "112") (name "/SHDN") (class "Default")
      (node (ref "P3") (pin "1") (pinfunction "1_1") (pintype "passive"))
      (node (ref "P3") (pin "3") (pinfunction "3_3") (pintype "passive"))
      (node (ref "P8") (pin "1") (pinfunction "1_1") (pintype "passive"))
      (node (ref "U1") (pin "4") (pinfunction "SHDN_4") (pintype "input"))
    )
    (net (code "113") (name "/VBUS") (class "Default")
      (node (ref "J4") (pin "A4") (pinfunction "VBUS_A_A4") (pintype "power_in"))
      (node (ref "J4") (pin "A9") (pinfunction "VBUS_A_A9") (pintype "power_in"))
      (node (ref "J4") (pin "B4") (pinfunction "VBUS_B_B4") (pintype "power_in"))
      (node (ref "J4") (pin "B9") (pinfunction "VBUS_B_B9") (pintype "power_in"))
      (node (ref "P16") (pin "1") (pinfunction "1_1") (pintype "passive"))
    )
    (net (code "114") (name "12V") (class "Default")
      (node (ref "C1") (pin "1") (pinfunction "1_1") (pintype "passive"))
      (node (ref "C2") (pin "1") (pinfunction "1_1") (pintype "passive"))
      (node (ref "L1") (pin "1") (pintype "passive"))
      (node (ref "P3") (pin "2") (pinfunction "2_2") (pintype "passive"))
      (node (ref "P6") (pin "1") (pinfunction "1_1") (pintype "passive"))
      (node (ref "P6") (pin "3") (pinfunction "3_3") (pintype "passive"))
      (node (ref "P8") (pin "3") (pinfunction "3_3") (pintype "passive"))
      (node (ref "U1") (pin "2") (pinfunction "V+_2") (pintype "input"))
    )
    (net (code "115") (name "GND") (class "Default")
      (node (ref "C1") (pin "2") (pinfunction "2_2") (pintype "passive"))
      (node (ref "C2") (pin "2") (pinfunction "2_2") (pintype "passive"))
      (node (ref "C3") (pin "2") (pinfunction "2_2") (pintype "passive"))
      (node (ref "C4") (pin "2") (pinfunction "2_2") (pintype "passive"))
      (node (ref "C5") (pin "2") (pinfunction "2_2") (pintype "passive"))
      (node (ref "J4") (pin "A1") (pinfunction "GND_A_A1") (pintype "power_in"))
      (node (ref "J4") (pin "A12") (pinfunction "GND_A_A12") (pintype "power_in"))
      (node (ref "J4") (pin "B1") (pinfunction "GND_B_B1") (pintype "power_in"))
      (node (ref "J4") (pin "B12") (pinfunction "GND_B_B12") (pintype "power_in"))
      (node (ref "J4") (pin "S1") (pinfunction "SHELL_GND_S1") (pintype "power_in"))
      (node (ref "J4") (pin "S2") (pinfunction "SHELL_GND_S2") (pintype "power_in"))
      (node (ref "J4") (pin "S3") (pinfunction "SHELL_GND_S3") (pintype "power_in"))
      (node (ref "J4") (pin "S4") (pinfunction "SHELL_GND_S4") (pintype "power_in"))
      (node (ref "P12") (pin "2") (pinfunction "2_2") (pintype "passive"))
      (node (ref "P13") (pin "2") (pinfunction "2_2") (pintype "passive"))
      (node (ref "P14") (pin "2") (pinfunction "2_2") (pintype "passive"))
      (node (ref "P15") (pin "2") (pinfunction "2_2") (pintype "passive"))
      (node (ref "P3") (pin "4") (pinfunction "4_4") (pintype "passive"))
      (node (ref "P6") (pin "2") (pinfunction "2_2") (pintype "passive"))
      (node (ref "P6") (pin "4") (pinfunction "4_4") (pintype "passive"))
      (node (ref "P7") (pin "2") (pinfunction "2_2") (pintype "passive"))
      (node (ref "P7") (pin "4") (pinfunction "4_4") (pintype "passive"))
      (node (ref "P8") (pin "2") (pinfunction "2_2") (pintype "passive"))
      (node (ref "P9") (pin "2") (pinfunction "2_2") (pintype "passive"))
      (node (ref "R2") (pin "2") (pinfunction "2_2") (pintype "passive"))
      (node (ref "R3") (pin "2") (pinfunction "2_2") (pintype "passive"))
      (node (ref "U1") (pin "6") (pinfunction "AGND_6") (pintype "power_in"))
      (node (ref "U1") (pin "7") (pinfunction "GND_7") (pintype "power_in"))
    )
    (net (code "116") (name "Net-(J2-D)") (class "Default")
      (node (ref "J2") (pin "2") (pinfunction "D_2") (pintype "passive"))
      (node (ref "L1") (pin "2") (pintype "passive"))
      (node (ref "U2") (pin "1") (pinfunction "A_1") (pintype "passive"))
    )
    (net (code "117") (name "Net-(J2-S)") (class "Default")
      (node (ref "J2") (pin "3") (pinfunction "S_3") (pintype "passive"))
      (node (ref "R2") (pin "1") (pinfunction "1_1") (pintype "passive"))
      (node (ref "U1") (pin "8") (pinfunction "CS_8") (pintype "input"))
    )
    (net (code "118") (name "Net-(U1-REF)") (class "Default")
      (node (ref "C5") (pin "1") (pinfunction "1_1") (pintype "passive"))
      (node (ref "U1") (pin "5") (pinfunction "REF_5") (pintype "output"))
    )
    (net (code "119") (name "VH") (class "Default")
      (node (ref "C3") (pin "1") (pinfunction "1_1") (pintype "passive"))
      (node (ref "P7") (pin "1") (pinfunction "1_1") (pintype "passive"))
      (node (ref "P7") (pin "3") (pinfunction "3_3") (pintype "passive"))
      (node (ref "P9") (pin "1") (pinfunction "1_1") (pintype "passive"))
      (node (ref "R1") (pin "1") (pinfunction "1_1") (pintype "passive"))
      (node (ref "U2") (pin "2") (pinfunction "C_2") (pintype "passive"))
    )
  )
)
